# JDA_Compact_Switch_D2PAK_V1.net
KiCad netlist of a schematic drawn in EAGLE
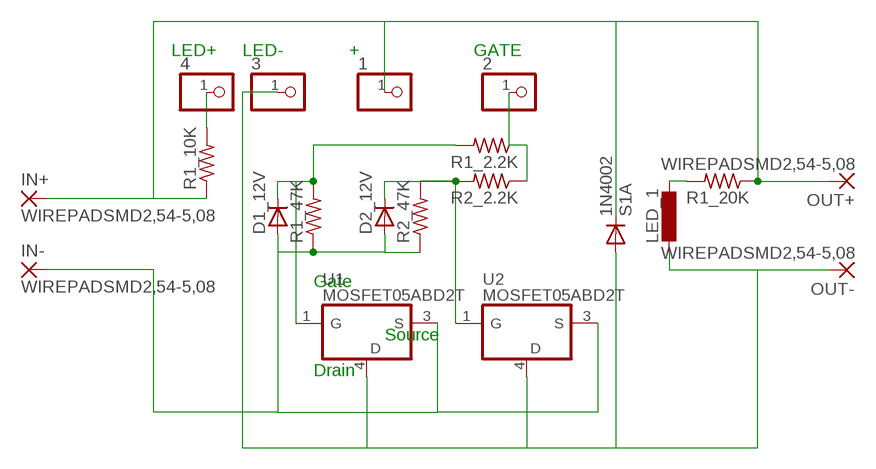
[diagram p0: schematic, sheet 1]

(export (version "E")
  (design (tool "Eeschema 10.0.6"))
  (components
    (comp (ref "1")
      (value "PINHD-1X1")
      (footprint "eagle-import:1X01")
      (libsource (lib "eagle-import") (part "PINHD-1X1"))
    )
    (comp (ref "1N4002")
      (value "S1A")
      (footprint "eagle-import:DO214AC")
      (fields (field (name "MF") "Fairchild"))
      (libsource (lib "eagle-import") (part "S1A"))
    )
    (comp (ref "2")
      (value "PINHD-1X1")
      (footprint "eagle-import:1X01")
      (libsource (lib "eagle-import") (part "PINHD-1X1"))
    )
    (comp (ref "3")
      (value "PINHD-1X1")
      (footprint "eagle-import:1X01")
      (libsource (lib "eagle-import") (part "PINHD-1X1"))
    )
    (comp (ref "4")
      (value "PINHD-1X1")
      (footprint "eagle-import:1X01")
      (libsource (lib "eagle-import") (part "PINHD-1X1"))
    )
    (comp (ref "D1_12V")
      (value "D-SOD-80")
      (footprint "eagle-import:SOD80")
      (libsource (lib "eagle-import") (part "D-SOD-80"))
    )
    (comp (ref "D2_12V")
      (value "D-SOD-80")
      (footprint "eagle-import:SOD80")
      (libsource (lib "eagle-import") (part "D-SOD-80"))
    )
    (comp (ref "IN+")
      (value "WIREPADSMD2,54-5,08")
      (footprint "eagle-import:SMD2,54-5,08")
      (libsource (lib "eagle-import") (part "WIREPADSMD2,54-5,08"))
    )
    (comp (ref "IN-")
      (value "WIREPADSMD2,54-5,08")
      (footprint "eagle-import:SMD2,54-5,08")
      (libsource (lib "eagle-import") (part "WIREPADSMD2,54-5,08"))
    )
    (comp (ref "LED_1")
      (value "L-EUL0805")
      (footprint "eagle-import:L0805")
      (libsource (lib "eagle-import") (part "L-EUL0805"))
    )
    (comp (ref "OUT+")
      (value "WIREPADSMD2,54-5,08")
      (footprint "eagle-import:SMD2,54-5,08")
      (libsource (lib "eagle-import") (part "WIREPADSMD2,54-5,08"))
    )
    (comp (ref "OUT-")
      (value "WIREPADSMD2,54-5,08")
      (footprint "eagle-import:SMD2,54-5,08")
      (libsource (lib "eagle-import") (part "WIREPADSMD2,54-5,08"))
    )
    (comp (ref "R1_2.2K")
      (value "R-US_M1206")
      (footprint "eagle-import:M1206")
      (libsource (lib "eagle-import") (part "resistor_R-US_M1206"))
    )
    (comp (ref "R1_10K")
      (value "R-US_M1206")
      (footprint "eagle-import:M1206")
      (libsource (lib "eagle-import") (part "resistor_R-US_M1206"))
    )
    (comp (ref "R1_20K")
      (value "R-US_R1206")
      (footprint "eagle-import:R1206")
      (libsource (lib "eagle-import") (part "R-US_R1206"))
    )
    (comp (ref "R1_47K")
      (value "R-US_M1206")
      (footprint "eagle-import:M1206")
      (libsource (lib "eagle-import") (part "resistor_R-US_M1206"))
    )
    (comp (ref "R2_2.2K")
      (value "R-US_M1206")
      (footprint "eagle-import:M1206")
      (libsource (lib "eagle-import") (part "resistor_R-US_M1206"))
    )
    (comp (ref "R2_47K")
      (value "R-US_M1206")
      (footprint "eagle-import:M1206")
      (libsource (lib "eagle-import") (part "resistor_R-US_M1206"))
    )
    (comp (ref "U1")
      (value "MOSFET05ABD2T")
      (footprint "eagle-import:D2PAK-3")
      (libsource (lib "eagle-import") (part "MOSFETD2T05AB"))
    )
    (comp (ref "U2")
      (value "MOSFET05ABD2T")
      (footprint "eagle-import:D2PAK-3")
      (libsource (lib "eagle-import") (part "MOSFETD2T05AB"))
    )
  )
  (nets
    (net (code "1") (name "Net-(2-Pad1)") (class "Default")
      (node (ref "2") (pin "1") (pinfunction "1_1") (pintype "passive"))
      (node (ref "R1_2.2K") (pin "1") (pinfunction "1_1") (pintype "passive"))
      (node (ref "R2_2.2K") (pin "1") (pinfunction "1_1") (pintype "passive"))
    )
    (net (code "2") (name "Net-(4-Pad1)") (class "Default")
      (node (ref "4") (pin "1") (pinfunction "1_1") (pintype "passive"))
      (node (ref "R1_10K") (pin "2") (pinfunction "2_2") (pintype "passive"))
    )
    (net (code "3") (name "Net-(IN+-P)") (class "Default")
      (node (ref "1") (pin "1") (pinfunction "1_1") (pintype "passive"))
      (node (ref "1N4002") (pin "C") (pinfunction "C_C") (pintype "passive"))
      (node (ref "IN+") (pin "1") (pinfunction "P_1") (pintype "passive"))
      (node (ref "OUT+") (pin "1") (pinfunction "P_1") (pintype "passive"))
      (node (ref "R1_10K") (pin "1") (pinfunction "1_1") (pintype "passive"))
      (node (ref "R1_20K") (pin "1") (pinfunction "1_1") (pintype "passive"))
    )
    (net (code "4") (name "Net-(IN--P)") (class "Default")
      (node (ref "D1_12V") (pin "A") (pinfunction "A_A") (pintype "passive"))
      (node (ref "D2_12V") (pin "A") (pinfunction "A_A") (pintype "passive"))
      (node (ref "IN-") (pin "1") (pinfunction "P_1") (pintype "passive"))
      (node (ref "R1_47K") (pin "1") (pinfunction "1_1") (pintype "passive"))
      (node (ref "R2_47K") (pin "1") (pinfunction "1_1") (pintype "passive"))
      (node (ref "U1") (pin "3") (pinfunction "S_3") (pintype "power_in"))
      (node (ref "U2") (pin "3") (pinfunction "S_3") (pintype "power_in"))
    )
    (net (code "5") (name "Net-(LED_1-Pad1)") (class "Default")
      (node (ref "LED_1") (pin "1") (pinfunction "1_1") (pintype "passive"))
      (node (ref "R1_20K") (pin "2") (pinfunction "2_2") (pintype "passive"))
    )
    (net (code "6") (name "Net-(OUT--P)") (class "Default")
      (node (ref "1N4002") (pin "A") (pinfunction "A_A") (pintype "passive"))
      (node (ref "3") (pin "1") (pinfunction "1_1") (pintype "passive"))
      (node (ref "LED_1") (pin "2") (pinfunction "2_2") (pintype "passive"))
      (node (ref "OUT-") (pin "1") (pinfunction "P_1") (pintype "passive"))
      (node (ref "U1") (pin "4") (pinfunction "GND_4") (pintype "power_in"))
      (node (ref "U2") (pin "4") (pinfunction "GND_4") (pintype "power_in"))
    )
    (net (code "7") (name "Net-(U1-G)") (class "Default")
      (node (ref "D1_12V") (pin "C") (pinfunction "C_C") (pintype "passive"))
      (node (ref "R1_2.2K") (pin "2") (pinfunction "2_2") (pintype "passive"))
      (node (ref "R1_47K") (pin "2") (pinfunction "2_2") (pintype "passive"))
      (node (ref "U1") (pin "1") (pinfunction "G_1") (pintype "power_in"))
    )
    (net (code "8") (name "Net-(U2-G)") (class "Default")
      (node (ref "D2_12V") (pin "C") (pinfunction "C_C") (pintype "passive"))
      (node (ref "R2_2.2K") (pin "2") (pinfunction "2_2") (pintype "passive"))
      (node (ref "R2_47K") (pin "2") (pinfunction "2_2") (pintype "passive"))
      (node (ref "U2") (pin "1") (pinfunction "G_1") (pintype "power_in"))
    )
  )
)
